# untitled2.net
KiCad netlist of a schematic drawn in EAGLE
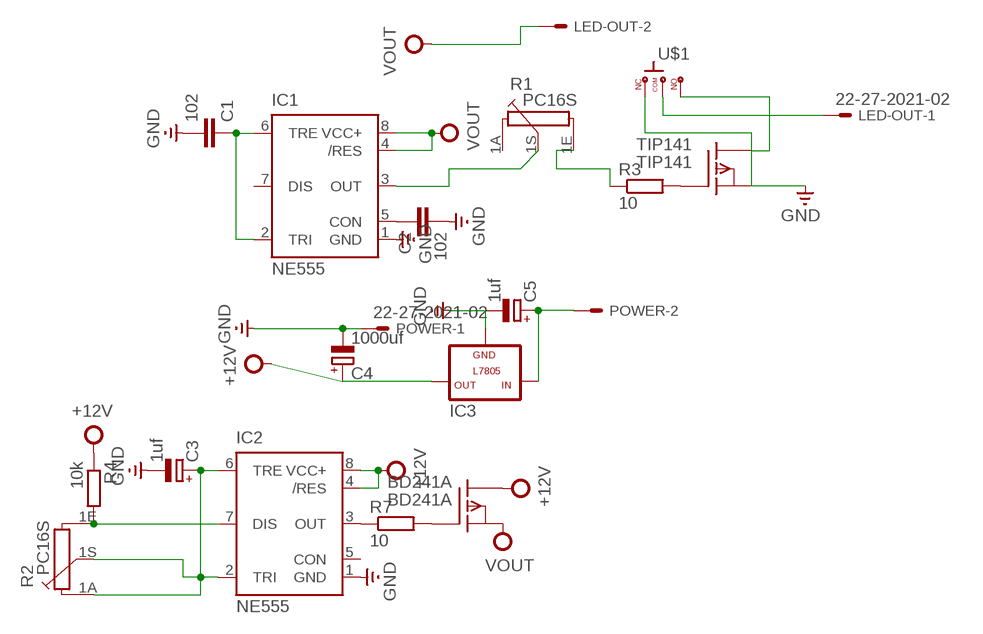
[diagram p0: schematic, sheet 1]

(export (version "E")
  (design (tool "Eeschema 10.0.6"))
  (components
    (comp (ref "BD241A")
      (value "BD241A")
      (footprint "eagle-import:TO220")
      (libsource (lib "eagle-import") (part "BUZ171"))
    )
    (comp (ref "C1")
      (value "102")
      (footprint "eagle-import:C050-024X044")
      (libsource (lib "eagle-import") (part "C-EU050-024X044"))
    )
    (comp (ref "C2")
      (value "102")
      (footprint "eagle-import:C050-024X044")
      (libsource (lib "eagle-import") (part "C-EU050-024X044"))
    )
    (comp (ref "C3")
      (value "1uf")
      (footprint "eagle-import:E5-4")
      (libsource (lib "eagle-import") (part "CPOL-EUE5-4"))
    )
    (comp (ref "C4")
      (value "1000uf")
      (footprint "eagle-import:E5-4")
      (libsource (lib "eagle-import") (part "CPOL-EUE5-4"))
    )
    (comp (ref "C5")
      (value "1uf")
      (footprint "eagle-import:E5-4")
      (libsource (lib "eagle-import") (part "CPOL-EUE5-4"))
    )
    (comp (ref "IC1")
      (value "NE555")
      (footprint "eagle-import:DIL-08")
      (libsource (lib "eagle-import") (part "NE555"))
    )
    (comp (ref "IC2")
      (value "NE555")
      (footprint "eagle-import:DIL-08")
      (libsource (lib "eagle-import") (part "NE555"))
    )
    (comp (ref "IC3")
      (value "L7805")
      (footprint "eagle-import:78XXL")
      (libsource (lib "eagle-import") (part "L7805"))
    )
    (comp (ref "LED-OUT")
      (value "22-27-2021-02")
      (footprint "eagle-import:6410-02")
      (libsource (lib "eagle-import") (part "22-?-0227-2021"))
    )
    (comp (ref "POWER")
      (value "22-27-2021-02")
      (footprint "eagle-import:6410-02")
      (libsource (lib "eagle-import") (part "22-?-0227-2021"))
    )
    (comp (ref "R1")
      (value "PC16S")
      (footprint "eagle-import:PC16S")
      (libsource (lib "eagle-import") (part "PC16S"))
    )
    (comp (ref "R2")
      (value "PC16S")
      (footprint "eagle-import:PC16S")
      (libsource (lib "eagle-import") (part "PC16S"))
    )
    (comp (ref "R3")
      (value "10")
      (footprint "eagle-import:0207_7")
      (libsource (lib "eagle-import") (part "R-EU_0207/7"))
    )
    (comp (ref "R4")
      (value "10k")
      (footprint "eagle-import:0207_7")
      (libsource (lib "eagle-import") (part "R-EU_0207/7"))
    )
    (comp (ref "R7")
      (value "10")
      (footprint "eagle-import:0207_7")
      (libsource (lib "eagle-import") (part "R-EU_0207/7"))
    )
    (comp (ref "TIP141")
      (value "TIP141")
      (footprint "eagle-import:TO220")
      (libsource (lib "eagle-import") (part "BUZ171"))
    )
    (comp (ref "U$1")
      (value "-SLIDERS")
      (footprint "eagle-import:CON3")
      (libsource (lib "eagle-import") (part "-SLIDERS"))
    )
  )
  (nets
    (net (code "1") (name "+12V") (class "Default")
      (node (ref "BD241A") (pin "2") (pinfunction "D_2") (pintype "passive"))
      (node (ref "C4") (pin "+") (pinfunction "+_+") (pintype "passive"))
      (node (ref "IC2") (pin "4") (pinfunction "/RES_4") (pintype "input"))
      (node (ref "IC2") (pin "8") (pinfunction "VCC+_8") (pintype "power_in"))
      (node (ref "IC3") (pin "OUT") (pinfunction "OUT_OUT") (pintype "passive"))
      (node (ref "R4") (pin "1") (pinfunction "1_1") (pintype "passive"))
    )
    (net (code "2") (name "GND") (class "Default")
      (node (ref "C1") (pin "2") (pinfunction "2_2") (pintype "passive"))
      (node (ref "C2") (pin "2") (pinfunction "2_2") (pintype "passive"))
      (node (ref "C3") (pin "-") (pinfunction "-_-") (pintype "passive"))
      (node (ref "C4") (pin "-") (pinfunction "-_-") (pintype "passive"))
      (node (ref "C5") (pin "-") (pinfunction "-_-") (pintype "passive"))
      (node (ref "IC1") (pin "1") (pinfunction "GND_1") (pintype "power_in"))
      (node (ref "IC2") (pin "1") (pinfunction "GND_1") (pintype "power_in"))
      (node (ref "IC3") (pin "GND") (pinfunction "GND_GND") (pintype "input"))
      (node (ref "POWER") (pin "1") (pinfunction "S_1") (pintype "passive"))
      (node (ref "TIP141") (pin "3") (pinfunction "S_3") (pintype "passive"))
      (node (ref "U$1") (pin "P$1") (pinfunction "1_P$1") (pintype "passive"))
    )
    (net (code "3") (name "Net-(BD241A-G)") (class "Default")
      (node (ref "BD241A") (pin "1") (pinfunction "G_1") (pintype "passive"))
      (node (ref "R7") (pin "2") (pinfunction "2_2") (pintype "passive"))
    )
    (net (code "4") (name "Net-(IC1-CON)") (class "Default")
      (node (ref "C2") (pin "1") (pinfunction "1_1") (pintype "passive"))
      (node (ref "IC1") (pin "5") (pinfunction "CON_5") (pintype "input"))
    )
    (net (code "5") (name "Net-(IC1-OUT)") (class "Default")
      (node (ref "IC1") (pin "3") (pinfunction "OUT_3") (pintype "output"))
      (node (ref "R1") (pin "1S") (pinfunction "1S_1S") (pintype "passive"))
    )
    (net (code "6") (name "Net-(IC1-TRE)") (class "Default")
      (node (ref "C1") (pin "1") (pinfunction "1_1") (pintype "passive"))
      (node (ref "IC1") (pin "2") (pinfunction "TRI_2") (pintype "input"))
      (node (ref "IC1") (pin "6") (pinfunction "TRE_6") (pintype "input"))
    )
    (net (code "7") (name "Net-(IC2-DIS)") (class "Default")
      (node (ref "IC2") (pin "7") (pinfunction "DIS_7") (pintype "input"))
      (node (ref "R2") (pin "1E") (pinfunction "1E_1E") (pintype "passive"))
      (node (ref "R4") (pin "2") (pinfunction "2_2") (pintype "passive"))
    )
    (net (code "8") (name "Net-(IC2-OUT)") (class "Default")
      (node (ref "IC2") (pin "3") (pinfunction "OUT_3") (pintype "output"))
      (node (ref "R7") (pin "1") (pinfunction "1_1") (pintype "passive"))
    )
    (net (code "9") (name "Net-(IC2-TRE)") (class "Default")
      (node (ref "C3") (pin "+") (pinfunction "+_+") (pintype "passive"))
      (node (ref "IC2") (pin "2") (pinfunction "TRI_2") (pintype "input"))
      (node (ref "IC2") (pin "6") (pinfunction "TRE_6") (pintype "input"))
      (node (ref "R2") (pin "1A") (pinfunction "1A_1A") (pintype "passive"))
      (node (ref "R2") (pin "1S") (pinfunction "1S_1S") (pintype "passive"))
    )
    (net (code "10") (name "Net-(LED-OUTA-S)") (class "Default")
      (node (ref "LED-OUT") (pin "1") (pinfunction "S_1") (pintype "passive"))
      (node (ref "U$1") (pin "P$2") (pinfunction "2_P$2") (pintype "passive"))
    )
    (net (code "11") (name "Net-(POWERB-S)") (class "Default")
      (node (ref "C5") (pin "+") (pinfunction "+_+") (pintype "passive"))
      (node (ref "IC3") (pin "IN") (pinfunction "IN_IN") (pintype "input"))
      (node (ref "POWER") (pin "2") (pinfunction "S_2") (pintype "passive"))
    )
    (net (code "12") (name "Net-(R1-Pad1E)") (class "Default")
      (node (ref "R1") (pin "1E") (pinfunction "1E_1E") (pintype "passive"))
      (node (ref "R3") (pin "1") (pinfunction "1_1") (pintype "passive"))
    )
    (net (code "13") (name "Net-(TIP141-D)") (class "Default")
      (node (ref "TIP141") (pin "2") (pinfunction "D_2") (pintype "passive"))
      (node (ref "U$1") (pin "P$3") (pinfunction "3_P$3") (pintype "passive"))
    )
    (net (code "14") (name "Net-(TIP141-G)") (class "Default")
      (node (ref "R3") (pin "2") (pinfunction "2_2") (pintype "passive"))
      (node (ref "TIP141") (pin "1") (pinfunction "G_1") (pintype "passive"))
    )
    (net (code "15") (name "VOUT") (class "Default")
      (node (ref "BD241A") (pin "3") (pinfunction "S_3") (pintype "passive"))
      (node (ref "IC1") (pin "4") (pinfunction "/RES_4") (pintype "input"))
      (node (ref "IC1") (pin "8") (pinfunction "VCC+_8") (pintype "power_in"))
      (node (ref "LED-OUT") (pin "2") (pinfunction "S_2") (pintype "passive"))
    )
    (net (code "16") (name "unconnected-(IC1-DIS-Pad7)") (class "Default")
      (node (ref "IC1") (pin "7") (pinfunction "DIS_7") (pintype "input"))
    )
    (net (code "17") (name "unconnected-(IC2-CON-Pad5)") (class "Default")
      (node (ref "IC2") (pin "5") (pinfunction "CON_5") (pintype "input"))
    )
    (net (code "18") (name "unconnected-(R1-Pad1A)") (class "Default")
      (node (ref "R1") (pin "1A") (pinfunction "1A_1A") (pintype "passive"))
    )
  )
)
